# usbcan.net
KiCad netlist of a schematic drawn in EAGLE
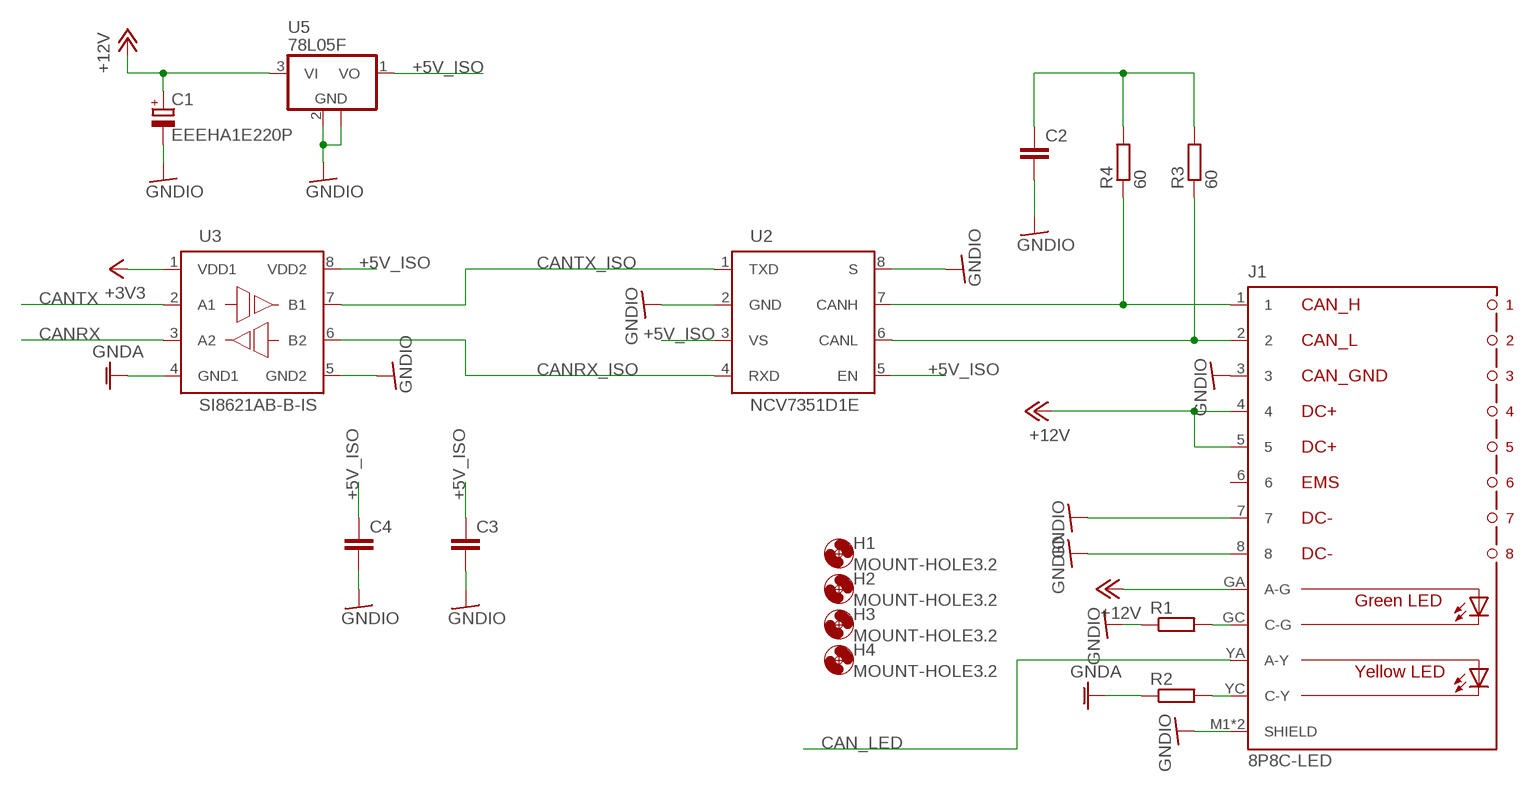
[diagram p0: schematic, sheet 1]
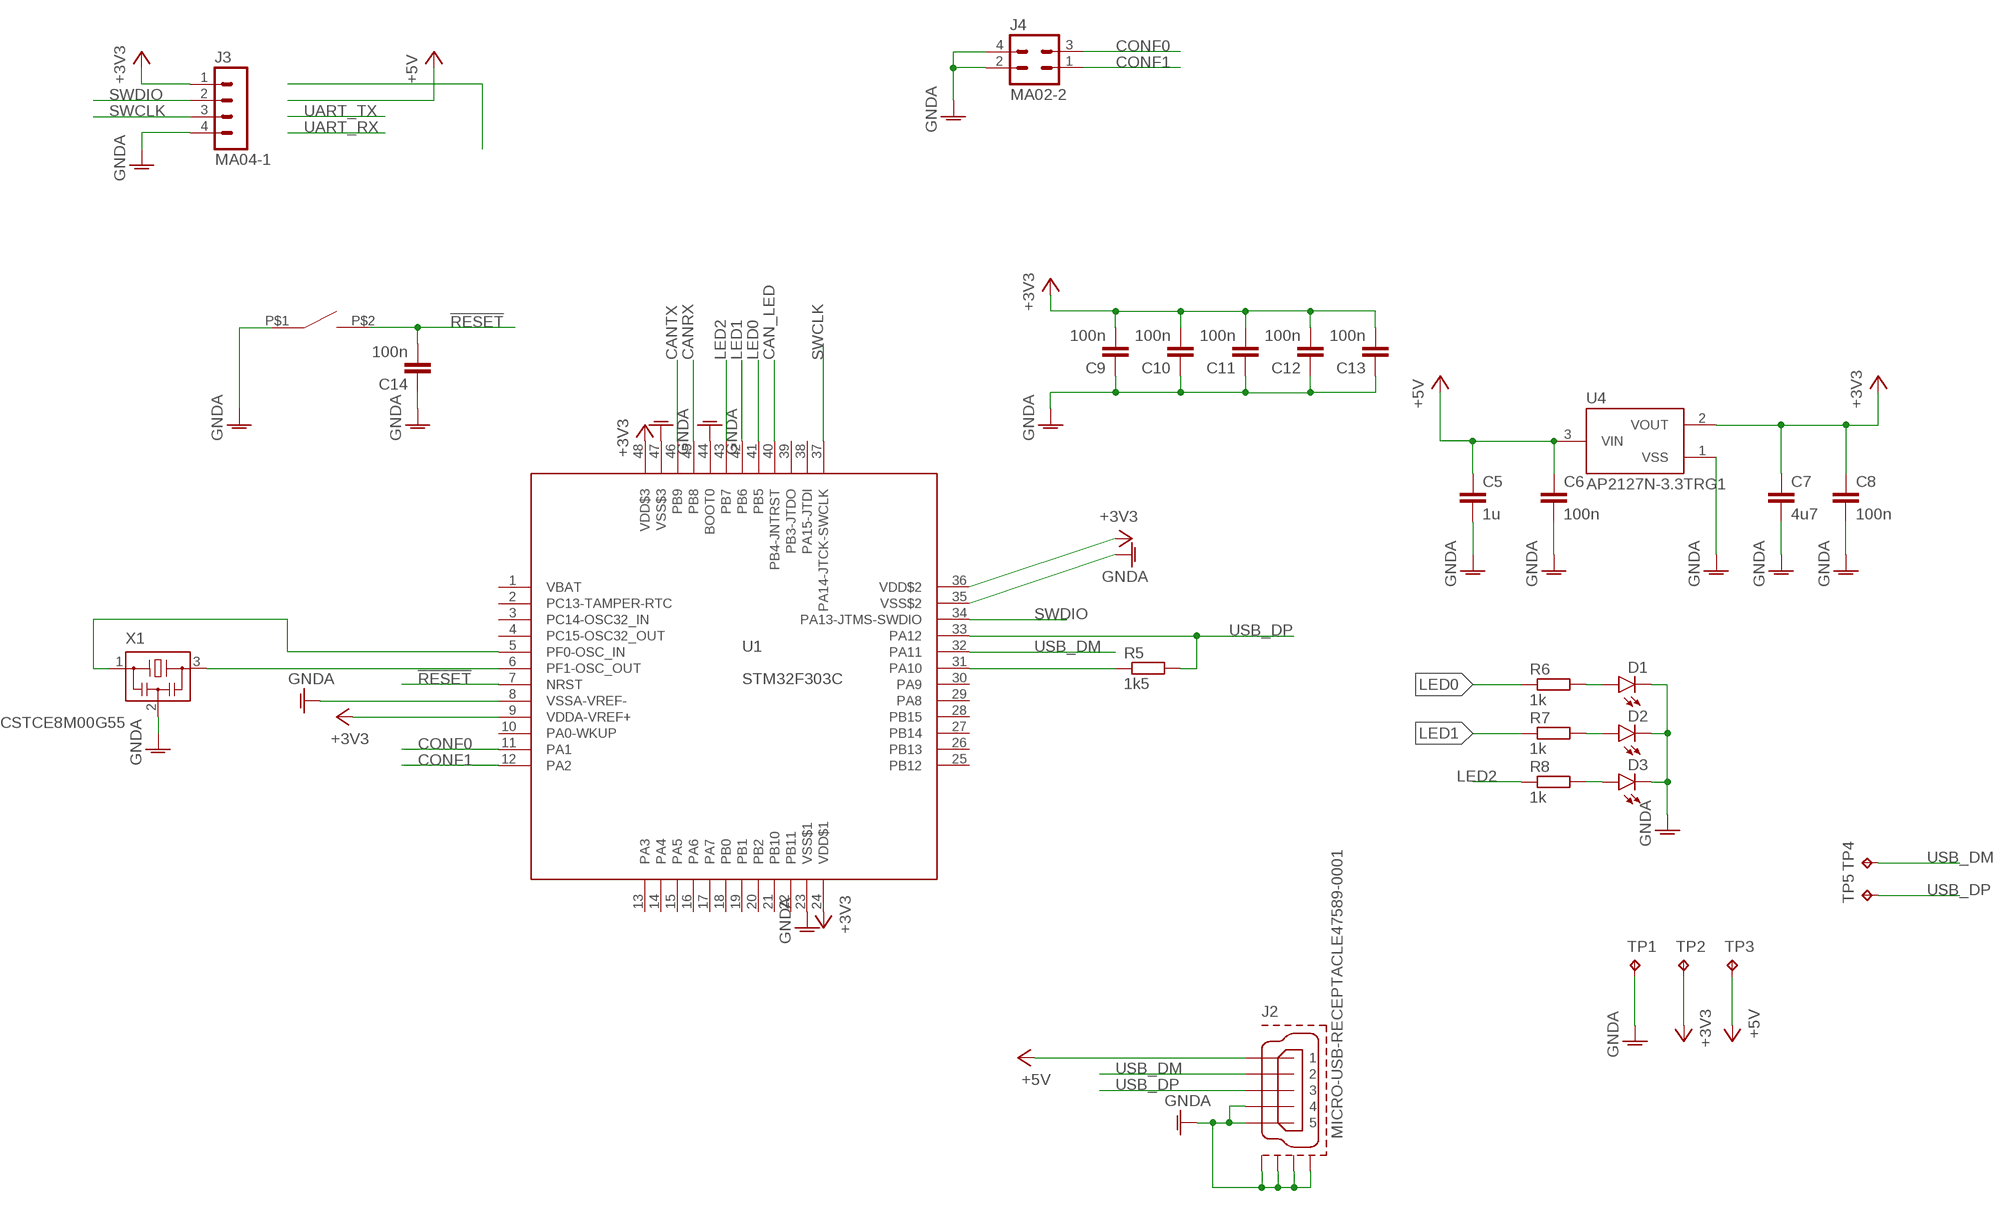
[diagram p1: schematic, sheet 2]

(export (version "E")
  (design (tool "Eeschema 10.0.6"))
  (components
    (comp (ref "C1")
      (value "EEEHA1E220P")
      (footprint "eagle-import:153CLV-0605")
      (libsource (lib "eagle-import") (part "CPOL-EU153CLV-0605"))
    )
    (comp (ref "C2")
      (value "C-EUC0603")
      (footprint "eagle-import:C0603")
      (libsource (lib "eagle-import") (part "rcl_334_C-EUC0603"))
    )
    (comp (ref "C3")
      (value "C-EUC0603")
      (footprint "eagle-import:C0603")
      (libsource (lib "eagle-import") (part "rcl_334_C-EUC0603"))
    )
    (comp (ref "C4")
      (value "C-EUC0603")
      (footprint "eagle-import:C0603")
      (libsource (lib "eagle-import") (part "rcl_334_C-EUC0603"))
    )
    (comp (ref "H1")
      (value "MOUNT-HOLE3.2")
      (footprint "eagle-import:3,2")
      (libsource (lib "eagle-import") (part "MOUNT-HOLE3.2"))
    )
    (comp (ref "H2")
      (value "MOUNT-HOLE3.2")
      (footprint "eagle-import:3,2")
      (libsource (lib "eagle-import") (part "MOUNT-HOLE3.2"))
    )
    (comp (ref "H3")
      (value "MOUNT-HOLE3.2")
      (footprint "eagle-import:3,2")
      (libsource (lib "eagle-import") (part "MOUNT-HOLE3.2"))
    )
    (comp (ref "H4")
      (value "MOUNT-HOLE3.2")
      (footprint "eagle-import:3,2")
      (libsource (lib "eagle-import") (part "MOUNT-HOLE3.2"))
    )
    (comp (ref "J1")
      (value "8P8C-LED")
      (footprint "eagle-import:8P8C-LED")
      (libsource (lib "eagle-import") (part "8P8C-LED"))
    )
    (comp (ref "R1")
      (value "R-EU_R0603")
      (footprint "eagle-import:R0603")
      (libsource (lib "eagle-import") (part "rcl_334_R-EU_R0603"))
    )
    (comp (ref "R2")
      (value "R-EU_R0603")
      (footprint "eagle-import:R0603")
      (libsource (lib "eagle-import") (part "rcl_334_R-EU_R0603"))
    )
    (comp (ref "R3")
      (value "60")
      (footprint "eagle-import:R0603")
      (libsource (lib "eagle-import") (part "rcl_334_R-EU_R0603"))
    )
    (comp (ref "R4")
      (value "60")
      (footprint "eagle-import:R0603")
      (libsource (lib "eagle-import") (part "rcl_334_R-EU_R0603"))
    )
    (comp (ref "U2")
      (value "NCV7351D1E")
      (footprint "eagle-import:SO08")
      (libsource (lib "eagle-import") (part "NCV7351D1E"))
    )
    (comp (ref "U3")
      (value "SI8621AB-B-IS")
      (footprint "eagle-import:SO08")
      (libsource (lib "eagle-import") (part "SI8621AB-B-IS"))
    )
    (comp (ref "U5")
      (value "78L05F")
      (footprint "eagle-import:SOT89")
      (libsource (lib "eagle-import") (part "78LF05"))
    )
    (comp (ref "C5")
      (value "1u")
      (footprint "eagle-import:C0603")
      (libsource (lib "eagle-import") (part "C-EUC0603"))
    )
    (comp (ref "C6")
      (value "100n")
      (footprint "eagle-import:C0603")
      (libsource (lib "eagle-import") (part "C-EUC0603"))
    )
    (comp (ref "C7")
      (value "4u7")
      (footprint "eagle-import:C0805")
      (libsource (lib "eagle-import") (part "C-EUC0805"))
    )
    (comp (ref "C8")
      (value "100n")
      (footprint "eagle-import:C0603")
      (libsource (lib "eagle-import") (part "C-EUC0603"))
    )
    (comp (ref "C9")
      (value "100n")
      (footprint "eagle-import:C0603")
      (libsource (lib "eagle-import") (part "C-EUC0603"))
    )
    (comp (ref "C10")
      (value "100n")
      (footprint "eagle-import:C0603")
      (libsource (lib "eagle-import") (part "C-EUC0603"))
    )
    (comp (ref "C11")
      (value "100n")
      (footprint "eagle-import:C0603")
      (libsource (lib "eagle-import") (part "C-EUC0603"))
    )
    (comp (ref "C12")
      (value "100n")
      (footprint "eagle-import:C0603")
      (libsource (lib "eagle-import") (part "C-EUC0603"))
    )
    (comp (ref "C13")
      (value "100n")
      (footprint "eagle-import:C0603")
      (libsource (lib "eagle-import") (part "C-EUC0603"))
    )
    (comp (ref "C14")
      (value "100n")
      (footprint "eagle-import:C0603")
      (libsource (lib "eagle-import") (part "C-EUC0603"))
    )
    (comp (ref "D1")
      (value "LEDCHIPLED_0805")
      (footprint "eagle-import:CHIPLED_0805")
      (libsource (lib "eagle-import") (part "LEDCHIPLED_0805"))
    )
    (comp (ref "D2")
      (value "LEDCHIPLED_0805")
      (footprint "eagle-import:CHIPLED_0805")
      (libsource (lib "eagle-import") (part "LEDCHIPLED_0805"))
    )
    (comp (ref "D3")
      (value "LEDCHIPLED_0805")
      (footprint "eagle-import:CHIPLED_0805")
      (libsource (lib "eagle-import") (part "LEDCHIPLED_0805"))
    )
    (comp (ref "J2")
      (value "MICRO-USB-RECEPTACLE47589-0001")
      (footprint "eagle-import:47589-0001")
      (libsource (lib "eagle-import") (part "MICRO-USB-RECEPTACLE47589-0001"))
    )
    (comp (ref "J3")
      (value "MA04-1")
      (footprint "eagle-import:MA04-1")
      (libsource (lib "eagle-import") (part "MA04-1"))
    )
    (comp (ref "J4")
      (value "MA02-2")
      (footprint "eagle-import:MA02-2W")
      (libsource (lib "eagle-import") (part "MA02-2"))
    )
    (comp (ref "R5")
      (value "1k5")
      (footprint "eagle-import:R0603")
      (libsource (lib "eagle-import") (part "R-EU_R0603"))
    )
    (comp (ref "R6")
      (value "1k")
      (footprint "eagle-import:R0603")
      (libsource (lib "eagle-import") (part "R-EU_R0603"))
    )
    (comp (ref "R7")
      (value "1k")
      (footprint "eagle-import:R0603")
      (libsource (lib "eagle-import") (part "R-EU_R0603"))
    )
    (comp (ref "R8")
      (value "1k")
      (footprint "eagle-import:R0603")
      (libsource (lib "eagle-import") (part "R-EU_R0603"))
    )
    (comp (ref "S1")
      (value "SWITCH_TACTILETOP")
      (footprint "eagle-import:SWITCH_TACTILE_3X6")
      (libsource (lib "eagle-import") (part "SWITCH_TACTILETOP"))
    )
    (comp (ref "TP1")
      (value "TPB1,27")
      (footprint "eagle-import:B1,27")
      (libsource (lib "eagle-import") (part "TPB1,27"))
    )
    (comp (ref "TP2")
      (value "TPB1,27")
      (footprint "eagle-import:B1,27")
      (libsource (lib "eagle-import") (part "TPB1,27"))
    )
    (comp (ref "TP3")
      (value "TPB1,27")
      (footprint "eagle-import:B1,27")
      (libsource (lib "eagle-import") (part "TPB1,27"))
    )
    (comp (ref "TP4")
      (value "TPB1,27")
      (footprint "eagle-import:B1,27")
      (libsource (lib "eagle-import") (part "TPB1,27"))
    )
    (comp (ref "TP5")
      (value "TPB1,27")
      (footprint "eagle-import:B1,27")
      (libsource (lib "eagle-import") (part "TPB1,27"))
    )
    (comp (ref "U1")
      (value "STM32F303C")
      (footprint "eagle-import:LQFP48")
      (libsource (lib "eagle-import") (part "STM32F303C"))
    )
    (comp (ref "U4")
      (value "AP2127N-3.3TRG1")
      (footprint "eagle-import:SOT95P240X110-3")
      (libsource (lib "eagle-import") (part "XC6206"))
    )
    (comp (ref "X1")
      (value "CSTCE8M00G55")
      (footprint "eagle-import:CSTCE8M00G55")
      (libsource (lib "eagle-import") (part "CSTCE8M00G55"))
    )
  )
  (nets
    (net (code "1") (name "+3V3") (class "Default")
      (node (ref "C10") (pin "2") (pinfunction "2_2") (pintype "passive"))
      (node (ref "C11") (pin "2") (pinfunction "2_2") (pintype "passive"))
      (node (ref "C12") (pin "2") (pinfunction "2_2") (pintype "passive"))
      (node (ref "C13") (pin "2") (pinfunction "2_2") (pintype "passive"))
      (node (ref "C7") (pin "1") (pinfunction "1_1") (pintype "passive"))
      (node (ref "C8") (pin "1") (pinfunction "1_1") (pintype "passive"))
      (node (ref "C9") (pin "2") (pinfunction "2_2") (pintype "passive"))
      (node (ref "J3") (pin "1") (pinfunction "1_1") (pintype "passive"))
      (node (ref "TP2") (pin "TP") (pinfunction "TP_TP") (pintype "input"))
      (node (ref "U1") (pin "24") (pinfunction "VDD$1_24") (pintype "passive"))
      (node (ref "U1") (pin "36") (pinfunction "VDD$2_36") (pintype "passive"))
      (node (ref "U1") (pin "48") (pinfunction "VDD$3_48") (pintype "passive"))
      (node (ref "U1") (pin "9") (pinfunction "VDDA-VREF+_9") (pintype "bidirectional"))
      (node (ref "U3") (pin "1") (pinfunction "VDD1_1") (pintype "power_in"))
      (node (ref "U4") (pin "2") (pinfunction "VOUT_2") (pintype "bidirectional"))
    )
    (net (code "2") (name "+5V") (class "Default")
      (node (ref "C5") (pin "1") (pinfunction "1_1") (pintype "passive"))
      (node (ref "C6") (pin "1") (pinfunction "1_1") (pintype "passive"))
      (node (ref "J2") (pin "1") (pinfunction "1_1") (pintype "input"))
      (node (ref "TP3") (pin "TP") (pinfunction "TP_TP") (pintype "input"))
      (node (ref "U4") (pin "3") (pinfunction "VIN_3") (pintype "bidirectional"))
    )
    (net (code "3") (name "+5V_ISO") (class "Default")
      (node (ref "C3") (pin "1") (pinfunction "1_1") (pintype "passive"))
      (node (ref "C4") (pin "1") (pinfunction "1_1") (pintype "passive"))
      (node (ref "U2") (pin "3") (pinfunction "VS_3") (pintype "power_in"))
      (node (ref "U2") (pin "5") (pinfunction "EN_5") (pintype "input"))
      (node (ref "U3") (pin "8") (pinfunction "VDD2_8") (pintype "power_in"))
      (node (ref "U5") (pin "1") (pinfunction "VO_1") (pintype "passive"))
    )
    (net (code "4") (name "+12V") (class "Default")
      (node (ref "C1") (pin "+") (pinfunction "+_+") (pintype "passive"))
      (node (ref "J1") (pin "4") (pinfunction "4_4") (pintype "input"))
      (node (ref "J1") (pin "5") (pinfunction "5_5") (pintype "input"))
      (node (ref "J1") (pin "GA") (pinfunction "A-G_GA") (pintype "passive"))
      (node (ref "U5") (pin "3") (pinfunction "VI_3") (pintype "input"))
    )
    (net (code "5") (name "CANRX") (class "Default")
      (node (ref "U1") (pin "45") (pinfunction "PB8_45") (pintype "bidirectional"))
      (node (ref "U3") (pin "3") (pinfunction "A2_3") (pintype "output"))
    )
    (net (code "6") (name "CANRX_ISO") (class "Default")
      (node (ref "U2") (pin "4") (pinfunction "RXD_4") (pintype "output"))
      (node (ref "U3") (pin "6") (pinfunction "B2_6") (pintype "output"))
    )
    (net (code "7") (name "CANTX") (class "Default")
      (node (ref "U1") (pin "46") (pinfunction "PB9_46") (pintype "bidirectional"))
      (node (ref "U3") (pin "2") (pinfunction "A1_2") (pintype "input"))
    )
    (net (code "8") (name "CANTX_ISO") (class "Default")
      (node (ref "U2") (pin "1") (pinfunction "TXD_1") (pintype "input"))
      (node (ref "U3") (pin "7") (pinfunction "B1_7") (pintype "output"))
    )
    (net (code "9") (name "CAN_LED") (class "Default")
      (node (ref "J1") (pin "YA") (pinfunction "A-Y_YA") (pintype "passive"))
      (node (ref "U1") (pin "40") (pinfunction "PB4-JNTRST_40") (pintype "bidirectional"))
    )
    (net (code "10") (name "CONF0") (class "Default")
      (node (ref "J4") (pin "3") (pinfunction "3_3") (pintype "passive"))
      (node (ref "U1") (pin "11") (pinfunction "PA1_11") (pintype "bidirectional"))
    )
    (net (code "11") (name "CONF1") (class "Default")
      (node (ref "J4") (pin "1") (pinfunction "1_1") (pintype "passive"))
      (node (ref "U1") (pin "12") (pinfunction "PA2_12") (pintype "bidirectional"))
    )
    (net (code "12") (name "GNDA") (class "Default")
      (node (ref "C10") (pin "1") (pinfunction "1_1") (pintype "passive"))
      (node (ref "C11") (pin "1") (pinfunction "1_1") (pintype "passive"))
      (node (ref "C12") (pin "1") (pinfunction "1_1") (pintype "passive"))
      (node (ref "C13") (pin "1") (pinfunction "1_1") (pintype "passive"))
      (node (ref "C14") (pin "1") (pinfunction "1_1") (pintype "passive"))
      (node (ref "C5") (pin "2") (pinfunction "2_2") (pintype "passive"))
      (node (ref "C6") (pin "2") (pinfunction "2_2") (pintype "passive"))
      (node (ref "C7") (pin "2") (pinfunction "2_2") (pintype "passive"))
      (node (ref "C8") (pin "2") (pinfunction "2_2") (pintype "passive"))
      (node (ref "C9") (pin "1") (pinfunction "1_1") (pintype "passive"))
      (node (ref "D1") (pin "C") (pinfunction "C_C") (pintype "passive"))
      (node (ref "D2") (pin "C") (pinfunction "C_C") (pintype "passive"))
      (node (ref "D3") (pin "C") (pinfunction "C_C") (pintype "passive"))
      (node (ref "J2") (pin "4") (pinfunction "4_4") (pintype "input"))
      (node (ref "J2") (pin "5") (pinfunction "5_5") (pintype "input"))
      (node (ref "J2") (pin "CASING1") (pinfunction "GND1_CASING1") (pintype "bidirectional"))
      (node (ref "J2") (pin "CASING2") (pinfunction "GND2_CASING2") (pintype "bidirectional"))
      (node (ref "J2") (pin "CASING3") (pinfunction "GND3_CASING3") (pintype "bidirectional"))
      (node (ref "J2") (pin "CASING4") (pinfunction "GND4_CASING4") (pintype "bidirectional"))
      (node (ref "J2") (pin "P$1") (pinfunction "GND1_P$1") (pintype "bidirectional"))
      (node (ref "J2") (pin "P$2") (pinfunction "GND1_P$2") (pintype "bidirectional"))
      (node (ref "J2") (pin "P$3") (pinfunction "GND2_P$3") (pintype "bidirectional"))
      (node (ref "J2") (pin "P$4") (pinfunction "GND2_P$4") (pintype "bidirectional"))
      (node (ref "J3") (pin "4") (pinfunction "4_4") (pintype "passive"))
      (node (ref "J4") (pin "2") (pinfunction "2_2") (pintype "passive"))
      (node (ref "J4") (pin "4") (pinfunction "4_4") (pintype "passive"))
      (node (ref "R2") (pin "1") (pinfunction "1_1") (pintype "passive"))
      (node (ref "S1") (pin "P$1") (pinfunction "1_P$1") (pintype "bidirectional"))
      (node (ref "TP1") (pin "TP") (pinfunction "TP_TP") (pintype "input"))
      (node (ref "U1") (pin "23") (pinfunction "VSS$1_23") (pintype "passive"))
      (node (ref "U1") (pin "35") (pinfunction "VSS$2_35") (pintype "passive"))
      (node (ref "U1") (pin "44") (pinfunction "BOOT0_44") (pintype "input"))
      (node (ref "U1") (pin "47") (pinfunction "VSS$3_47") (pintype "passive"))
      (node (ref "U1") (pin "8") (pinfunction "VSSA-VREF-_8") (pintype "bidirectional"))
      (node (ref "U3") (pin "4") (pinfunction "GND1_4") (pintype "power_in"))
      (node (ref "U4") (pin "1") (pinfunction "VSS_1") (pintype "bidirectional"))
      (node (ref "X1") (pin "2") (pinfunction "2_2") (pintype "passive"))
    )
    (net (code "13") (name "GNDIO") (class "Default")
      (node (ref "C1") (pin "-") (pinfunction "-_-") (pintype "passive"))
      (node (ref "C2") (pin "2") (pinfunction "2_2") (pintype "passive"))
      (node (ref "C3") (pin "2") (pinfunction "2_2") (pintype "passive"))
      (node (ref "C4") (pin "2") (pinfunction "2_2") (pintype "passive"))
      (node (ref "J1") (pin "3") (pinfunction "3_3") (pintype "input"))
      (node (ref "J1") (pin "7") (pinfunction "7_7") (pintype "input"))
      (node (ref "J1") (pin "8") (pinfunction "8_8") (pintype "input"))
      (node (ref "J1") (pin "M1") (pinfunction "SHIELD_M1") (pintype "passive"))
      (node (ref "J1") (pin "M2") (pinfunction "SHIELD_M2") (pintype "passive"))
      (node (ref "R1") (pin "1") (pinfunction "1_1") (pintype "passive"))
      (node (ref "U2") (pin "2") (pinfunction "GND_2") (pintype "power_in"))
      (node (ref "U2") (pin "8") (pinfunction "S_8") (pintype "input"))
      (node (ref "U3") (pin "5") (pinfunction "GND2_5") (pintype "power_in"))
      (node (ref "U5") (pin "2") (pinfunction "GND_2") (pintype "passive"))
      (node (ref "U5") (pin "2@1") (pinfunction "GND_2@1") (pintype "passive"))
    )
    (net (code "14") (name "LED0") (class "Default")
      (node (ref "R6") (pin "1") (pinfunction "1_1") (pintype "passive"))
      (node (ref "U1") (pin "41") (pinfunction "PB5_41") (pintype "bidirectional"))
    )
    (net (code "15") (name "LED1") (class "Default")
      (node (ref "R7") (pin "1") (pinfunction "1_1") (pintype "passive"))
      (node (ref "U1") (pin "42") (pinfunction "PB6_42") (pintype "bidirectional"))
    )
    (net (code "16") (name "LED2") (class "Default")
      (node (ref "R8") (pin "1") (pinfunction "1_1") (pintype "passive"))
      (node (ref "U1") (pin "43") (pinfunction "PB7_43") (pintype "bidirectional"))
    )
    (net (code "17") (name "Net-(C2-Pad1)") (class "Default")
      (node (ref "C2") (pin "1") (pinfunction "1_1") (pintype "passive"))
      (node (ref "R3") (pin "2") (pinfunction "2_2") (pintype "passive"))
      (node (ref "R4") (pin "2") (pinfunction "2_2") (pintype "passive"))
    )
    (net (code "18") (name "Net-(D1-PadA)") (class "Default")
      (node (ref "D1") (pin "A") (pinfunction "A_A") (pintype "passive"))
      (node (ref "R6") (pin "2") (pinfunction "2_2") (pintype "passive"))
    )
    (net (code "19") (name "Net-(D2-PadA)") (class "Default")
      (node (ref "D2") (pin "A") (pinfunction "A_A") (pintype "passive"))
      (node (ref "R7") (pin "2") (pinfunction "2_2") (pintype "passive"))
    )
    (net (code "20") (name "Net-(D3-PadA)") (class "Default")
      (node (ref "D3") (pin "A") (pinfunction "A_A") (pintype "passive"))
      (node (ref "R8") (pin "2") (pinfunction "2_2") (pintype "passive"))
    )
    (net (code "21") (name "Net-(J1-C-G)") (class "Default")
      (node (ref "J1") (pin "GC") (pinfunction "C-G_GC") (pintype "passive"))
      (node (ref "R1") (pin "2") (pinfunction "2_2") (pintype "passive"))
    )
    (net (code "22") (name "Net-(J1-C-Y)") (class "Default")
      (node (ref "J1") (pin "YC") (pinfunction "C-Y_YC") (pintype "passive"))
      (node (ref "R2") (pin "2") (pinfunction "2_2") (pintype "passive"))
    )
    (net (code "23") (name "Net-(U1-PA10)") (class "Default")
      (node (ref "R5") (pin "1") (pinfunction "1_1") (pintype "passive"))
      (node (ref "U1") (pin "31") (pinfunction "PA10_31") (pintype "bidirectional"))
    )
    (net (code "24") (name "Net-(U1-PF0-OSC_IN)") (class "Default")
      (node (ref "U1") (pin "5") (pinfunction "PF0-OSC_IN_5") (pintype "input"))
      (node (ref "X1") (pin "1") (pinfunction "1_1") (pintype "passive"))
    )
    (net (code "25") (name "Net-(U1-PF1-OSC_OUT)") (class "Default")
      (node (ref "U1") (pin "6") (pinfunction "PF1-OSC_OUT_6") (pintype "output"))
      (node (ref "X1") (pin "3") (pinfunction "3_3") (pintype "passive"))
    )
    (net (code "26") (name "Net-(U2-CANH)") (class "Default")
      (node (ref "J1") (pin "1") (pinfunction "1_1") (pintype "input"))
      (node (ref "R4") (pin "1") (pinfunction "1_1") (pintype "passive"))
      (node (ref "U2") (pin "7") (pinfunction "CANH_7") (pintype "output"))
    )
    (net (code "27") (name "Net-(U2-CANL)") (class "Default")
      (node (ref "J1") (pin "2") (pinfunction "2_2") (pintype "input"))
      (node (ref "R3") (pin "1") (pinfunction "1_1") (pintype "passive"))
      (node (ref "U2") (pin "6") (pinfunction "CANL_6") (pintype "output"))
    )
    (net (code "28") (name "SWCLK") (class "Default")
      (node (ref "J3") (pin "3") (pinfunction "3_3") (pintype "passive"))
      (node (ref "U1") (pin "37") (pinfunction "PA14-JTCK-SWCLK_37") (pintype "bidirectional"))
    )
    (net (code "29") (name "SWDIO") (class "Default")
      (node (ref "J3") (pin "2") (pinfunction "2_2") (pintype "passive"))
      (node (ref "U1") (pin "34") (pinfunction "PA13-JTMS-SWDIO_34") (pintype "bidirectional"))
    )
    (net (code "32") (name "USB_DM") (class "Default")
      (node (ref "J2") (pin "2") (pinfunction "2_2") (pintype "input"))
      (node (ref "TP4") (pin "TP") (pinfunction "TP_TP") (pintype "input"))
      (node (ref "U1") (pin "32") (pinfunction "PA11_32") (pintype "bidirectional"))
    )
    (net (code "33") (name "USB_DP") (class "Default")
      (node (ref "J2") (pin "3") (pinfunction "3_3") (pintype "input"))
      (node (ref "R5") (pin "2") (pinfunction "2_2") (pintype "passive"))
      (node (ref "TP5") (pin "TP") (pinfunction "TP_TP") (pintype "input"))
      (node (ref "U1") (pin "33") (pinfunction "PA12_33") (pintype "bidirectional"))
    )
    (net (code "34") (name "unconnected-(J1-Pad6)") (class "Default")
      (node (ref "J1") (pin "6") (pinfunction "6_6") (pintype "input"))
    )
    (net (code "35") (name "unconnected-(U1-PA0-WKUP-Pad10)") (class "Default")
      (node (ref "U1") (pin "10") (pinfunction "PA0-WKUP_10") (pintype "bidirectional"))
    )
    (net (code "36") (name "unconnected-(U1-PA3-Pad13)") (class "Default")
      (node (ref "U1") (pin "13") (pinfunction "PA3_13") (pintype "bidirectional"))
    )
    (net (code "37") (name "unconnected-(U1-PA4-Pad14)") (class "Default")
      (node (ref "U1") (pin "14") (pinfunction "PA4_14") (pintype "bidirectional"))
    )
    (net (code "38") (name "unconnected-(U1-PA5-Pad15)") (class "Default")
      (node (ref "U1") (pin "15") (pinfunction "PA5_15") (pintype "bidirectional"))
    )
    (net (code "39") (name "unconnected-(U1-PA6-Pad16)") (class "Default")
      (node (ref "U1") (pin "16") (pinfunction "PA6_16") (pintype "bidirectional"))
    )
    (net (code "40") (name "unconnected-(U1-PA7-Pad17)") (class "Default")
      (node (ref "U1") (pin "17") (pinfunction "PA7_17") (pintype "bidirectional"))
    )
    (net (code "41") (name "unconnected-(U1-PA8-Pad29)") (class "Default")
      (node (ref "U1") (pin "29") (pinfunction "PA8_29") (pintype "bidirectional"))
    )
    (net (code "42") (name "unconnected-(U1-PA9-Pad30)") (class "Default")
      (node (ref "U1") (pin "30") (pinfunction "PA9_30") (pintype "bidirectional"))
    )
    (net (code "43") (name "unconnected-(U1-PA15-JTDI-Pad38)") (class "Default")
      (node (ref "U1") (pin "38") (pinfunction "PA15-JTDI_38") (pintype "bidirectional"))
    )
    (net (code "44") (name "unconnected-(U1-PB0-Pad18)") (class "Default")
      (node (ref "U1") (pin "18") (pinfunction "PB0_18") (pintype "bidirectional"))
    )
    (net (code "45") (name "unconnected-(U1-PB1-Pad19)") (class "Default")
      (node (ref "U1") (pin "19") (pinfunction "PB1_19") (pintype "bidirectional"))
    )
    (net (code "46") (name "unconnected-(U1-PB2-Pad20)") (class "Default")
      (node (ref "U1") (pin "20") (pinfunction "PB2_20") (pintype "bidirectional"))
    )
    (net (code "47") (name "unconnected-(U1-PB3-JTDO-Pad39)") (class "Default")
      (node (ref "U1") (pin "39") (pinfunction "PB3-JTDO_39") (pintype "bidirectional"))
    )
    (net (code "48") (name "unconnected-(U1-PB10-Pad21)") (class "Default")
      (node (ref "U1") (pin "21") (pinfunction "PB10_21") (pintype "bidirectional"))
    )
    (net (code "49") (name "unconnected-(U1-PB11-Pad22)") (class "Default")
      (node (ref "U1") (pin "22") (pinfunction "PB11_22") (pintype "bidirectional"))
    )
    (net (code "50") (name "unconnected-(U1-PB12-Pad25)") (class "Default")
      (node (ref "U1") (pin "25") (pinfunction "PB12_25") (pintype "bidirectional"))
    )
    (net (code "51") (name "unconnected-(U1-PB13-Pad26)") (class "Default")
      (node (ref "U1") (pin "26") (pinfunction "PB13_26") (pintype "bidirectional"))
    )
    (net (code "52") (name "unconnected-(U1-PB14-Pad27)") (class "Default")
      (node (ref "U1") (pin "27") (pinfunction "PB14_27") (pintype "bidirectional"))
    )
    (net (code "53") (name "unconnected-(U1-PB15-Pad28)") (class "Default")
      (node (ref "U1") (pin "28") (pinfunction "PB15_28") (pintype "bidirectional"))
    )
    (net (code "54") (name "unconnected-(U1-PC13-TAMPER-RTC-Pad2)") (class "Default")
      (node (ref "U1") (pin "2") (pinfunction "PC13-TAMPER-RTC_2") (pintype "bidirectional"))
    )
    (net (code "55") (name "unconnected-(U1-PC14-OSC32_IN-Pad3)") (class "Default")
      (node (ref "U1") (pin "3") (pinfunction "PC14-OSC32_IN_3") (pintype "bidirectional"))
    )
    (net (code "56") (name "unconnected-(U1-PC15-OSC32_OUT-Pad4)") (class "Default")
      (node (ref "U1") (pin "4") (pinfunction "PC15-OSC32_OUT_4") (pintype "bidirectional"))
    )
    (net (code "57") (name "unconnected-(U1-VBAT-Pad1)") (class "Default")
      (node (ref "U1") (pin "1") (pinfunction "VBAT_1") (pintype "passive"))
    )
    (net (code "58") (name "~{RESET}") (class "Default")
      (node (ref "C14") (pin "2") (pinfunction "2_2") (pintype "passive"))
      (node (ref "S1") (pin "P$2") (pinfunction "2_P$2") (pintype "bidirectional"))
      (node (ref "U1") (pin "7") (pinfunction "NRST_7") (pintype "bidirectional"))
    )
  )
)
